# design.net
KiCad netlist of a schematic drawn in Altium Designer
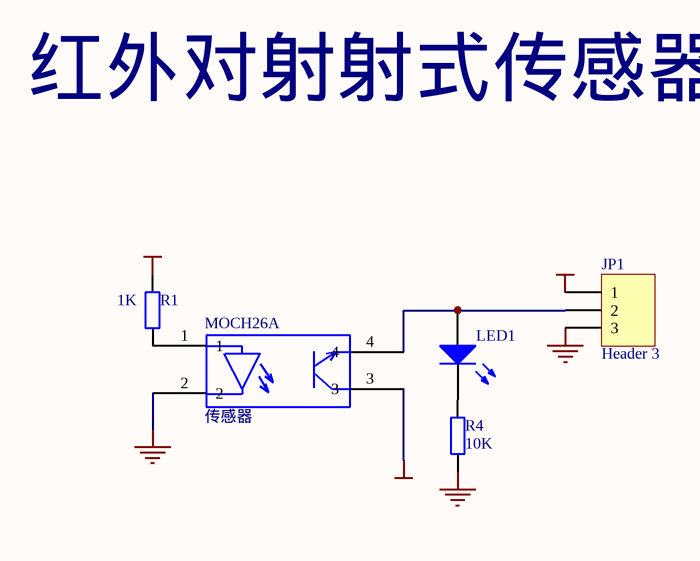
[diagram p0: 对射式红外传感器.SchDoc]

(export (version "E")
  (design (tool "Eeschema 10.0.6"))
  (components
    (comp (ref "JP1")
      (value "Header 3")
      (footprint "HDR1X3")
      (description "Header, 3-Pin")
      (fields (field (name "PUBLISHER") "Altium Limited"))
      (libsource (lib "Miscellaneous Connectors") (part "Header 3"))
    )
    (comp (ref "LED1")
      (value "~")
      (footprint "HDR1X2")
      (description "Typical BLUE SiC LED")
      (fields (field (name "PUBLISHER") "Altium Limited"))
      (libsource (lib "Miscellaneous Devices") (part "LED3"))
    )
    (comp (ref "MOCH26A") (value "传感器") (footprint "MOCH26A") (libsource (lib "传感器") (part "传感器")))
    (comp (ref "R1")
      (value "1K")
      (footprint "C1608-0603")
      (description "Resistor")
      (fields (field (name "PUBLISHER") "Altium Limited"))
      (libsource (lib "Miscellaneous Devices") (part "Res2"))
    )
    (comp (ref "R4")
      (value "10K")
      (footprint "C1608-0603")
      (description "Resistor")
      (fields (field (name "PUBLISHER") "Altium Limited"))
      (libsource (lib "") (part "Res2_1"))
    )
  )
  (nets
    (net (code "1") (name "GND") (class "Default")
      (node (ref "JP1") (pin "3") (pinfunction "3_3") (pintype "passive"))
      (node (ref "MOCH26A") (pin "2") (pinfunction "2_2") (pintype "passive"))
      (node (ref "R4") (pin "2") (pinfunction "2_2") (pintype "passive"))
    )
    (net (code "2") (name "Net-(LED1-A)") (class "Default")
      (node (ref "JP1") (pin "2") (pinfunction "2_2") (pintype "passive"))
      (node (ref "LED1") (pin "1") (pinfunction "A_1") (pintype "passive"))
      (node (ref "MOCH26A") (pin "4") (pinfunction "4_4") (pintype "passive"))
    )
    (net (code "3") (name "Net-(LED1-K)") (class "Default")
      (node (ref "LED1") (pin "2") (pinfunction "K_2") (pintype "passive"))
      (node (ref "R4") (pin "1") (pinfunction "1_1") (pintype "passive"))
    )
    (net (code "4") (name "Net-(MOCH26A-Pad1)") (class "Default")
      (node (ref "MOCH26A") (pin "1") (pinfunction "1_1") (pintype "passive"))
      (node (ref "R1") (pin "1") (pinfunction "1_1") (pintype "passive"))
    )
    (net (code "5") (name "VCC") (class "Default")
      (node (ref "JP1") (pin "1") (pinfunction "1_1") (pintype "passive"))
      (node (ref "MOCH26A") (pin "3") (pinfunction "3_3") (pintype "passive"))
      (node (ref "R1") (pin "2") (pinfunction "2_2") (pintype "passive"))
    )
  )
)
